# pcd_-_Copia.net
KiCad netlist of a schematic drawn in EAGLE
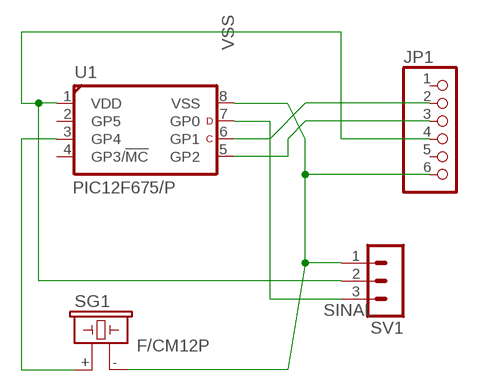
[diagram p0: schematic, sheet 1]

(export (version "E")
  (design (tool "Eeschema 10.0.6"))
  (components
    (comp (ref "JP1")
      (value "PINHD-1X6")
      (footprint "eagle-import:1X06")
      (libsource (lib "eagle-import") (part "PINHD-1X6"))
    )
    (comp (ref "SG1")
      (value "F/CM12P")
      (footprint "eagle-import:F_CM12P")
      (libsource (lib "eagle-import") (part "F/CM12P"))
    )
    (comp (ref "SV1")
      (value "MA03-1")
      (footprint "eagle-import:MA03-1")
      (libsource (lib "eagle-import") (part "MA03-1"))
    )
    (comp (ref "U1")
      (value "PIC12F675/P")
      (footprint "eagle-import:DIL8-P")
      (libsource (lib "eagle-import") (part "PIC12F675/P"))
    )
  )
  (nets
    (net (code "1") (name "/SINAL") (class "Default")
      (node (ref "SV1") (pin "3") (pinfunction "3_3") (pintype "passive"))
      (node (ref "U1") (pin "7") (pinfunction "GP0_7") (pintype "bidirectional"))
    )
    (net (code "2") (name "/VSS") (class "Default")
      (node (ref "JP1") (pin "6") (pinfunction "6_6") (pintype "passive"))
      (node (ref "SG1") (pin "-") (pinfunction "2_-") (pintype "passive"))
      (node (ref "SV1") (pin "1") (pinfunction "1_1") (pintype "passive"))
      (node (ref "U1") (pin "8") (pinfunction "VSS_8") (pintype "passive"))
    )
    (net (code "3") (name "Net-(SG1-1)") (class "Default")
      (node (ref "SG1") (pin "+") (pinfunction "1_+") (pintype "passive"))
      (node (ref "U1") (pin "3") (pinfunction "GP4_3") (pintype "bidirectional"))
    )
    (net (code "4") (name "Net-(U1-GP1)") (class "Default")
      (node (ref "JP1") (pin "2") (pinfunction "2_2") (pintype "passive"))
      (node (ref "U1") (pin "6") (pinfunction "GP1_6") (pintype "bidirectional"))
    )
    (net (code "5") (name "Net-(U1-GP2)") (class "Default")
      (node (ref "JP1") (pin "3") (pinfunction "3_3") (pintype "passive"))
      (node (ref "U1") (pin "5") (pinfunction "GP2_5") (pintype "bidirectional"))
    )
    (net (code "6") (name "Net-(U1-VDD)") (class "Default")
      (node (ref "JP1") (pin "4") (pinfunction "4_4") (pintype "passive"))
      (node (ref "SV1") (pin "2") (pinfunction "2_2") (pintype "passive"))
      (node (ref "U1") (pin "1") (pinfunction "VDD_1") (pintype "passive"))
    )
    (net (code "7") (name "unconnected-(JP1-Pad1)") (class "Default")
      (node (ref "JP1") (pin "1") (pinfunction "1_1") (pintype "passive"))
    )
    (net (code "8") (name "unconnected-(JP1-Pad5)") (class "Default")
      (node (ref "JP1") (pin "5") (pinfunction "5_5") (pintype "passive"))
    )
    (net (code "9") (name "unconnected-(U1-GP3{slash}~{MC}-Pad4)") (class "Default")
      (node (ref "U1") (pin "4") (pinfunction "GP3/~{MC}_4") (pintype "bidirectional"))
    )
    (net (code "10") (name "unconnected-(U1-GP5-Pad2)") (class "Default")
      (node (ref "U1") (pin "2") (pinfunction "GP5_2") (pintype "bidirectional"))
    )
  )
)
